# Relay_off_delay.net
KiCad netlist of a schematic drawn in Altium Designer
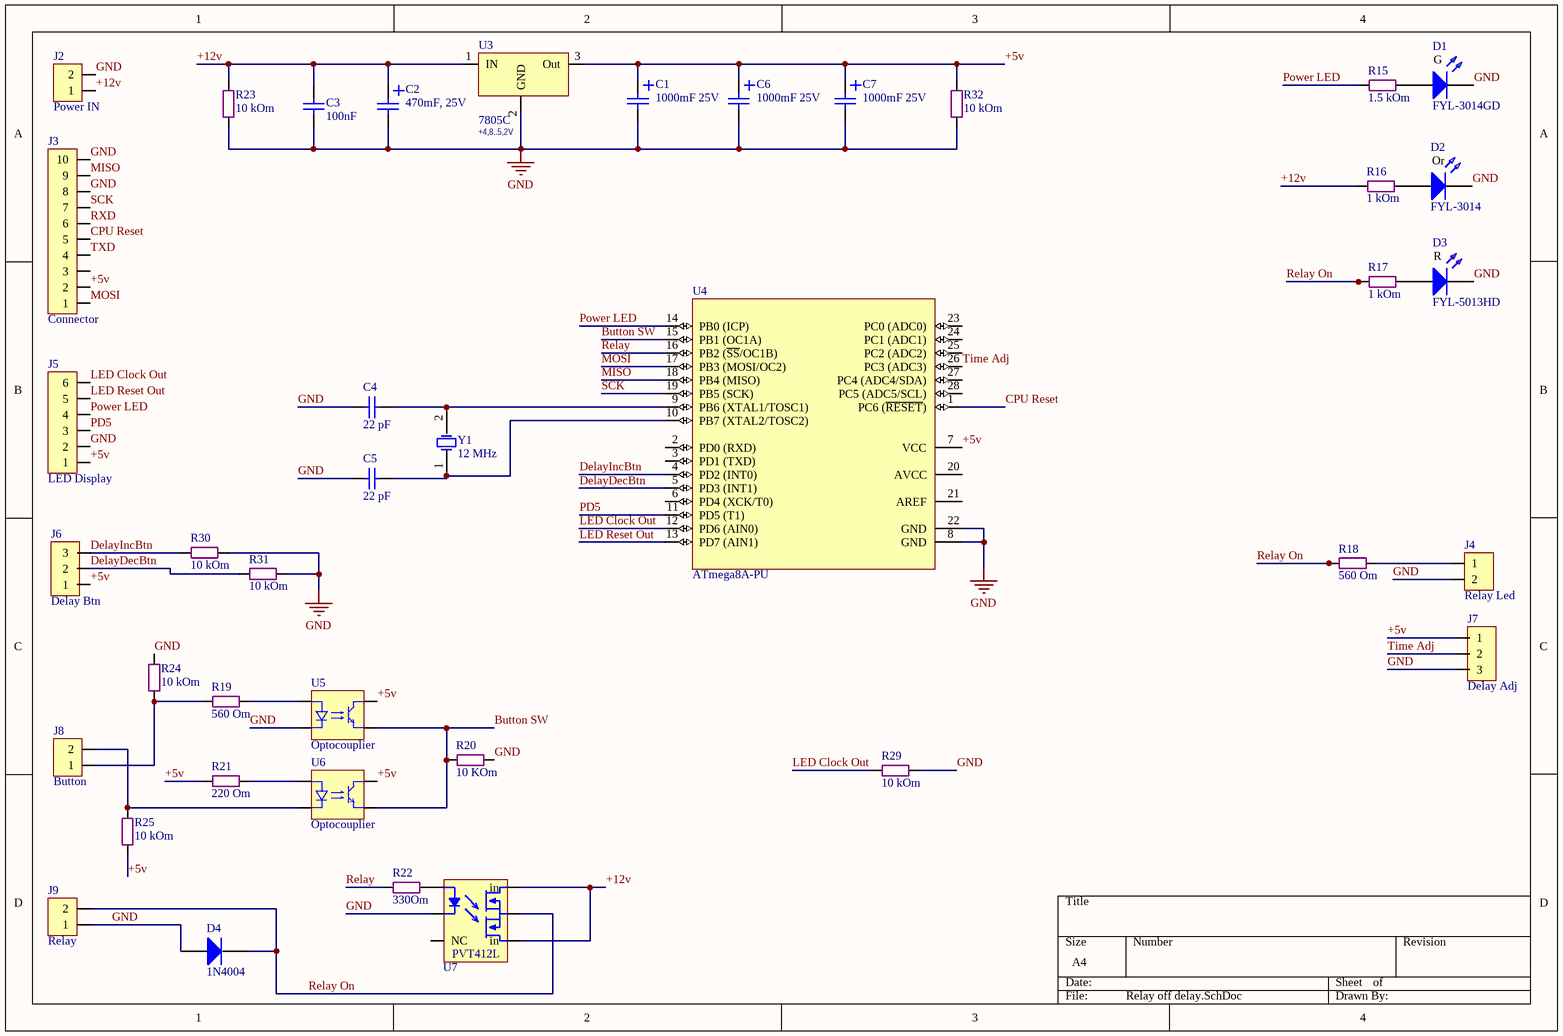
[diagram p0: Relay off delay.SchDoc]

(export (version "E")
  (design (tool "Eeschema 10.0.6"))
  (components
    (comp (ref "C1")
      (value "1000mF 25V")
      (footprint "Capacitor:Cap E p5.08mm D10.2mm (3p)")
      (description "Capacitor")
      (libsource (lib "Capacitor") (part "Cap E 1000mF x 25V"))
    )
    (comp (ref "C2")
      (value "470mF, 25V")
      (footprint "Capacitor:Cap E p3.5mm D8xH12")
      (description "Capacitor")
      (libsource (lib "Capacitor") (part "Cap E 470mF x 25V"))
    )
    (comp (ref "C3")
      (value "100nF")
      (footprint "Capacitor:Cap P5.08MM (3p) disk2")
      (description "Capacitor")
      (libsource (lib "Capacitor") (part "Cap Ceramic"))
    )
    (comp (ref "C4")
      (value "22 pF")
      (footprint "Capacitor:Cap P5.08MM (3p) disk2")
      (description "Capacitor")
      (libsource (lib "Capacitor") (part "Cap Ceramic"))
    )
    (comp (ref "C5")
      (value "22 pF")
      (footprint "Capacitor:Cap P5.08MM (3p) disk2")
      (description "Capacitor")
      (libsource (lib "Capacitor") (part "Cap Ceramic"))
    )
    (comp (ref "C6")
      (value "1000mF 25V")
      (footprint "Capacitor:Cap E p5.08mm D10.2mm (3p)")
      (description "Capacitor")
      (libsource (lib "Capacitor") (part "Cap E 1000mF x 25V"))
    )
    (comp (ref "C7")
      (value "1000mF 25V")
      (footprint "Capacitor:Cap E p5.08mm D10.2mm (3p)")
      (description "Capacitor")
      (libsource (lib "Capacitor") (part "Cap E 1000mF x 25V"))
    )
    (comp (ref "D1")
      (value "FYL-3014GD")
      (footprint "LED:LED Round 3mm Green")
      (description "2.1v 10mA, 15-30mCd")
      (libsource (lib "LED") (part "Led Round 3mm Green"))
    )
    (comp (ref "D2")
      (value "FYL-3014")
      (footprint "LED:LED Round 3mm Yellow")
      (description "2.1v 10mA, 30mCd")
      (libsource (lib "LED") (part "Led Round 3mm Orange"))
    )
    (comp (ref "D3")
      (value "FYL-5013HD")
      (footprint "LED:LED Round 3mm red")
      (description "2.25v 10mA, 5mCd")
      (libsource (lib "LED") (part "Led Round 3mm Red"))
    )
    (comp (ref "D4")
      (value "1N4004")
      (footprint "Diodes:Diode DO-35")
      (description "1 Amp General Purpose Rectifier")
      (libsource (lib "Diodes") (part "Diode 1N4004"))
    )
    (comp (ref "J2")
      (value "Power IN")
      (footprint "Connector:CWF-2 R")
      (description "CWF series")
      (libsource (lib "Connector") (part "CWF-2 (R)"))
    )
    (comp (ref "J3")
      (value "Connector")
      (footprint "Connector:LINE 2.54 x 10D (2 x 5) - BH")
      (description "Vert, Dbl line, Male")
      (libsource (lib "Connector") (part "PLD-10 (2 x 5)"))
    )
    (comp (ref "J4")
      (value "Relay Led")
      (footprint "Connector:CWF-2 R")
      (description "CWF series")
      (libsource (lib "") (part "CWF-2 (R)_1"))
    )
    (comp (ref "J5")
      (value "LED Display")
      (footprint "Connector:Molex Micro-Fit 3.0 - 6 pin D R")
      (description "Horisontal, Dbl line, Male - 3mm")
      (libsource (lib "Connector") (part "Micro-Fit 6R (2x3)"))
    )
    (comp (ref "J6")
      (value "Delay Btn")
      (footprint "Connector:WF-3")
      (description "Standart Fan MB's Connector")
      (libsource (lib "") (part "WF-3_1"))
    )
    (comp (ref "J7")
      (value "Delay Adj")
      (footprint "Connector:WF-3")
      (description "Standart Fan MB's Connector")
      (libsource (lib "Connector") (part "WF-3"))
    )
    (comp (ref "J8")
      (value "Button")
      (footprint "Connector:CWF-2 R")
      (description "CWF series")
      (libsource (lib "Connector") (part "CWF-2 (R)"))
    )
    (comp (ref "J9")
      (value "Relay")
      (footprint "Connector:CWF-2 R")
      (description "CWF series")
      (libsource (lib "Connector") (part "CWF-2 (R)"))
    )
    (comp (ref "R15")
      (value "1.5 kOm")
      (footprint "SMD 0805 (2012)")
      (libsource (lib "PassiveComponents") (part "Res SMD 0805"))
    )
    (comp (ref "R16")
      (value "1 kOm")
      (footprint "SMD 0805 (2012)")
      (libsource (lib "PassiveComponents") (part "Res SMD 0805"))
    )
    (comp (ref "R17")
      (value "1 kOm")
      (footprint "SMD 0805 (2012)")
      (libsource (lib "PassiveComponents") (part "Res SMD 0805"))
    )
    (comp (ref "R18")
      (value "560 Om")
      (footprint "SMD 0805 (2012)")
      (libsource (lib "PassiveComponents") (part "Res SMD 0805"))
    )
    (comp (ref "R19")
      (value "560 Om")
      (footprint "SMD 0805 (2012)")
      (libsource (lib "PassiveComponents") (part "Res SMD 0805"))
    )
    (comp (ref "R20")
      (value "10 KOm")
      (footprint "SMD 0805 (2012)")
      (libsource (lib "PassiveComponents") (part "Res SMD 0805"))
    )
    (comp (ref "R21")
      (value "220 Om")
      (footprint "SMD 0805 (2012)")
      (libsource (lib "PassiveComponents") (part "Res SMD 0805"))
    )
    (comp (ref "R22")
      (value "330Om")
      (footprint "PassiveComponents:SMD 1206 (3216)")
      (libsource (lib "PassiveComponents") (part "Res All Types"))
    )
    (comp (ref "R23")
      (value "10 kOm")
      (footprint "PassiveComponents:SMD 0805 (2012)")
      (libsource (lib "PassiveComponents") (part "Res All Types"))
    )
    (comp (ref "R24")
      (value "10 kOm")
      (footprint "PassiveComponents:SMD 0805 (2012)")
      (libsource (lib "PassiveComponents") (part "Res All Types"))
    )
    (comp (ref "R25")
      (value "10 kOm")
      (footprint "PassiveComponents:SMD 0805 (2012)")
      (libsource (lib "PassiveComponents") (part "Res All Types"))
    )
    (comp (ref "R29")
      (value "10 kOm")
      (footprint "PassiveComponents:Res p7.62 (4p) 0.25w")
      (libsource (lib "PassiveComponents") (part "Res All Types"))
    )
    (comp (ref "R30")
      (value "10 kOm")
      (footprint "PassiveComponents:Res p7.62 (4p) 0.25w")
      (libsource (lib "PassiveComponents") (part "Res All Types"))
    )
    (comp (ref "R31")
      (value "10 kOm")
      (footprint "PassiveComponents:Res p7.62 (4p) 0.25w")
      (libsource (lib "PassiveComponents") (part "Res All Types"))
    )
    (comp (ref "R32")
      (value "10 kOm")
      (footprint "PassiveComponents:SMD 0805 (2012)")
      (libsource (lib "PassiveComponents") (part "Res All Types"))
    )
    (comp (ref "U3")
      (value "7805C")
      (footprint "GeneralCases:D-PAK")
      (description "Voltage Regulator")
      (fields (field (name "MANUFACTURER") "Интеграл") (field (name "V OUT") "+4,8..5,2V"))
      (libsource (lib "PowerAdjusment") (part "7805C"))
    )
    (comp (ref "U4")
      (value "ATmega8A-PU")
      (footprint "28P3")
      (fields (field (name "PUBLISHER") "Altium Limited"))
      (libsource (lib "Atmel Microcontroller 8-Bit megaAVR") (part "ATmega8A-PU"))
    )
    (comp (ref "U5")
      (value "Optocouplier")
      (footprint "GeneralCases:DIP-4")
      (libsource (lib "Transistor") (part "Optocouplier LTV 817B"))
    )
    (comp (ref "U6")
      (value "Optocouplier")
      (footprint "GeneralCases:DIP-4")
      (libsource (lib "Transistor") (part "Optocouplier LTV 817B"))
    )
    (comp (ref "U7")
      (value "PVT412L")
      (footprint "GeneralCases:DIP-6")
      (description "Opto relay 2 chanel, MOSFET")
      (libsource (lib "Transistor") (part "Opto Rlay PVT412L"))
    )
    (comp (ref "Y1")
      (value "12 MHz")
      (footprint "PassiveComponents:XTAL - 2")
      (description "Crystal Oscillator")
      (fields (field (name "PUBLISHER") "Altium Limited"))
      (libsource (lib "PassiveComponents") (part "XTAL"))
    )
  )
  (nets
    (net (code "1") (name "/+5v") (class "Default")
      (node (ref "C1") (pin "1") (pinfunction "1_1") (pintype "passive"))
      (node (ref "C6") (pin "1") (pinfunction "1_1") (pintype "passive"))
      (node (ref "C7") (pin "1") (pinfunction "1_1") (pintype "passive"))
      (node (ref "J3") (pin "2") (pinfunction "2_2") (pintype "passive"))
      (node (ref "J5") (pin "1") (pinfunction "1_1") (pintype "passive"))
      (node (ref "J6") (pin "1") (pinfunction "1_1") (pintype "passive"))
      (node (ref "J7") (pin "1") (pinfunction "1_1") (pintype "passive"))
      (node (ref "R21") (pin "1") (pinfunction "1_1") (pintype "passive"))
      (node (ref "R25") (pin "1") (pinfunction "1_1") (pintype "passive"))
      (node (ref "R32") (pin "2") (pinfunction "2_2") (pintype "passive"))
      (node (ref "U3") (pin "3") (pinfunction "Out_3") (pintype "power_in"))
      (node (ref "U4") (pin "7") (pinfunction "VCC_7") (pintype "power_in"))
      (node (ref "U5") (pin "3") (pinfunction "3_3") (pintype "passive"))
      (node (ref "U6") (pin "3") (pinfunction "3_3") (pintype "passive"))
    )
    (net (code "2") (name "/+12v") (class "Default")
      (node (ref "C2") (pin "1") (pinfunction "1_1") (pintype "passive"))
      (node (ref "C3") (pin "1") (pinfunction "1_1") (pintype "passive"))
      (node (ref "J2") (pin "1") (pinfunction "1_1") (pintype "passive"))
      (node (ref "R16") (pin "1") (pinfunction "1_1") (pintype "passive"))
      (node (ref "R23") (pin "2") (pinfunction "2_2") (pintype "passive"))
      (node (ref "U3") (pin "1") (pinfunction "IN_1") (pintype "power_in"))
      (node (ref "U7") (pin "4") (pinfunction "in_4") (pintype "passive"))
      (node (ref "U7") (pin "6") (pinfunction "in_6") (pintype "passive"))
    )
    (net (code "3") (name "/Button SW") (class "Default")
      (node (ref "R20") (pin "1") (pinfunction "1_1") (pintype "passive"))
      (node (ref "U4") (pin "15") (pinfunction "PB1_(OC1A)_15") (pintype "bidirectional"))
      (node (ref "U5") (pin "4") (pinfunction "4_4") (pintype "passive"))
      (node (ref "U6") (pin "4") (pinfunction "4_4") (pintype "passive"))
    )
    (net (code "4") (name "/CPU Reset") (class "Default")
      (node (ref "J3") (pin "5") (pinfunction "5_5") (pintype "passive"))
      (node (ref "U4") (pin "1") (pinfunction "PC6_(~{RESET})_1") (pintype "bidirectional"))
    )
    (net (code "5") (name "/DelayDecBtn") (class "Default")
      (node (ref "J6") (pin "2") (pinfunction "2_2") (pintype "passive"))
      (node (ref "R31") (pin "2") (pinfunction "2_2") (pintype "passive"))
      (node (ref "U4") (pin "5") (pinfunction "PD3_(INT1)_5") (pintype "bidirectional"))
    )
    (net (code "6") (name "/DelayIncBtn") (class "Default")
      (node (ref "J6") (pin "3") (pinfunction "3_3") (pintype "passive"))
      (node (ref "R30") (pin "2") (pinfunction "2_2") (pintype "passive"))
      (node (ref "U4") (pin "4") (pinfunction "PD2_(INT0)_4") (pintype "bidirectional"))
    )
    (net (code "7") (name "/LED Clock Out") (class "Default")
      (node (ref "J5") (pin "6") (pinfunction "6_6") (pintype "passive"))
      (node (ref "R29") (pin "1") (pinfunction "1_1") (pintype "passive"))
      (node (ref "U4") (pin "12") (pinfunction "PD6_(AIN0)_12") (pintype "bidirectional"))
    )
    (net (code "8") (name "/LED Reset Out") (class "Default")
      (node (ref "J5") (pin "5") (pinfunction "5_5") (pintype "passive"))
      (node (ref "U4") (pin "13") (pinfunction "PD7_(AIN1)_13") (pintype "bidirectional"))
    )
    (net (code "9") (name "/MISO") (class "Default")
      (node (ref "J3") (pin "9") (pinfunction "9_9") (pintype "passive"))
      (node (ref "U4") (pin "18") (pinfunction "PB4_(MISO)_18") (pintype "bidirectional"))
    )
    (net (code "10") (name "/MOSI") (class "Default")
      (node (ref "J3") (pin "1") (pinfunction "1_1") (pintype "passive"))
      (node (ref "U4") (pin "17") (pinfunction "PB3_(MOSI/OC2)_17") (pintype "bidirectional"))
    )
    (net (code "11") (name "/PD5") (class "Default")
      (node (ref "J5") (pin "3") (pinfunction "3_3") (pintype "passive"))
      (node (ref "U4") (pin "11") (pinfunction "PD5_(T1)_11") (pintype "bidirectional"))
    )
    (net (code "12") (name "/Power LED") (class "Default")
      (node (ref "J5") (pin "4") (pinfunction "4_4") (pintype "passive"))
      (node (ref "R15") (pin "1") (pinfunction "1_1") (pintype "passive"))
      (node (ref "U4") (pin "14") (pinfunction "PB0_(ICP)_14") (pintype "bidirectional"))
    )
    (net (code "13") (name "/RXD") (class "Default")
      (node (ref "J3") (pin "6") (pinfunction "6_6") (pintype "passive"))
    )
    (net (code "14") (name "/Relay") (class "Default")
      (node (ref "R22") (pin "1") (pinfunction "1_1") (pintype "passive"))
      (node (ref "U4") (pin "16") (pinfunction "PB2_(~{SS}/OC1B)_16") (pintype "bidirectional"))
    )
    (net (code "15") (name "/Relay On") (class "Default")
      (node (ref "D4") (pin "K") (pinfunction "K_K") (pintype "passive"))
      (node (ref "J9") (pin "2") (pinfunction "2_2") (pintype "passive"))
      (node (ref "R17") (pin "1") (pinfunction "1_1") (pintype "passive"))
      (node (ref "R18") (pin "1") (pinfunction "1_1") (pintype "passive"))
      (node (ref "U7") (pin "5") (pinfunction "5_5") (pintype "passive"))
    )
    (net (code "16") (name "/SCK") (class "Default")
      (node (ref "J3") (pin "7") (pinfunction "7_7") (pintype "passive"))
      (node (ref "U4") (pin "19") (pinfunction "PB5_(SCK)_19") (pintype "bidirectional"))
    )
    (net (code "17") (name "/TXD") (class "Default")
      (node (ref "J3") (pin "4") (pinfunction "4_4") (pintype "passive"))
    )
    (net (code "18") (name "/Time Adj") (class "Default")
      (node (ref "J7") (pin "2") (pinfunction "2_2") (pintype "passive"))
      (node (ref "U4") (pin "26") (pinfunction "PC3_(ADC3)_26") (pintype "bidirectional"))
    )
    (net (code "19") (name "GND") (class "Default")
      (node (ref "C1") (pin "2") (pinfunction "2_2") (pintype "passive"))
      (node (ref "C2") (pin "2") (pinfunction "2_2") (pintype "passive"))
      (node (ref "C3") (pin "2") (pinfunction "2_2") (pintype "passive"))
      (node (ref "C4") (pin "1") (pinfunction "1_1") (pintype "passive"))
      (node (ref "C5") (pin "1") (pinfunction "1_1") (pintype "passive"))
      (node (ref "C6") (pin "2") (pinfunction "2_2") (pintype "passive"))
      (node (ref "C7") (pin "2") (pinfunction "2_2") (pintype "passive"))
      (node (ref "D1") (pin "K") (pinfunction "K_K") (pintype "passive"))
      (node (ref "D2") (pin "K") (pinfunction "K_K") (pintype "passive"))
      (node (ref "D3") (pin "K") (pinfunction "K_K") (pintype "passive"))
      (node (ref "D4") (pin "A") (pinfunction "A_A") (pintype "passive"))
      (node (ref "J2") (pin "2") (pinfunction "2_2") (pintype "passive"))
      (node (ref "J3") (pin "10") (pinfunction "10_10") (pintype "passive"))
      (node (ref "J3") (pin "8") (pinfunction "8_8") (pintype "passive"))
      (node (ref "J4") (pin "2") (pinfunction "2_2") (pintype "passive"))
      (node (ref "J5") (pin "2") (pinfunction "2_2") (pintype "passive"))
      (node (ref "J7") (pin "3") (pinfunction "3_3") (pintype "passive"))
      (node (ref "J9") (pin "1") (pinfunction "1_1") (pintype "passive"))
      (node (ref "R20") (pin "2") (pinfunction "2_2") (pintype "passive"))
      (node (ref "R23") (pin "1") (pinfunction "1_1") (pintype "passive"))
      (node (ref "R24") (pin "2") (pinfunction "2_2") (pintype "passive"))
      (node (ref "R29") (pin "2") (pinfunction "2_2") (pintype "passive"))
      (node (ref "R30") (pin "1") (pinfunction "1_1") (pintype "passive"))
      (node (ref "R31") (pin "1") (pinfunction "1_1") (pintype "passive"))
      (node (ref "R32") (pin "1") (pinfunction "1_1") (pintype "passive"))
      (node (ref "U3") (pin "2") (pinfunction "GND_2") (pintype "passive"))
      (node (ref "U4") (pin "22") (pinfunction "GND_22") (pintype "power_in"))
      (node (ref "U4") (pin "8") (pinfunction "GND_8") (pintype "power_in"))
      (node (ref "U5") (pin "2") (pinfunction "2_2") (pintype "passive"))
      (node (ref "U7") (pin "2") (pinfunction "2_2") (pintype "passive"))
    )
    (net (code "20") (name "Net-(D1-PadA)") (class "Default")
      (node (ref "D1") (pin "A") (pinfunction "A_A") (pintype "passive"))
      (node (ref "R15") (pin "2") (pinfunction "2_2") (pintype "passive"))
    )
    (net (code "21") (name "Net-(D2-PadA)") (class "Default")
      (node (ref "D2") (pin "A") (pinfunction "A_A") (pintype "passive"))
      (node (ref "R16") (pin "2") (pinfunction "2_2") (pintype "passive"))
    )
    (net (code "22") (name "Net-(D3-PadA)") (class "Default")
      (node (ref "D3") (pin "A") (pinfunction "A_A") (pintype "passive"))
      (node (ref "R17") (pin "2") (pinfunction "2_2") (pintype "passive"))
    )
    (net (code "23") (name "Net-(J4-Pad1)") (class "Default")
      (node (ref "J4") (pin "1") (pinfunction "1_1") (pintype "passive"))
      (node (ref "R18") (pin "2") (pinfunction "2_2") (pintype "passive"))
    )
    (net (code "24") (name "Net-(J8-Pad1)") (class "Default")
      (node (ref "J8") (pin "1") (pinfunction "1_1") (pintype "passive"))
      (node (ref "R19") (pin "1") (pinfunction "1_1") (pintype "passive"))
      (node (ref "R24") (pin "1") (pinfunction "1_1") (pintype "passive"))
    )
    (net (code "25") (name "Net-(J8-Pad2)") (class "Default")
      (node (ref "J8") (pin "2") (pinfunction "2_2") (pintype "passive"))
      (node (ref "R25") (pin "2") (pinfunction "2_2") (pintype "passive"))
      (node (ref "U6") (pin "2") (pinfunction "2_2") (pintype "passive"))
    )
    (net (code "26") (name "Net-(R19-Pad2)") (class "Default")
      (node (ref "R19") (pin "2") (pinfunction "2_2") (pintype "passive"))
      (node (ref "U5") (pin "1") (pinfunction "1_1") (pintype "passive"))
    )
    (net (code "27") (name "Net-(R21-Pad2)") (class "Default")
      (node (ref "R21") (pin "2") (pinfunction "2_2") (pintype "passive"))
      (node (ref "U6") (pin "1") (pinfunction "1_1") (pintype "passive"))
    )
    (net (code "28") (name "Net-(R22-Pad2)") (class "Default")
      (node (ref "R22") (pin "2") (pinfunction "2_2") (pintype "passive"))
      (node (ref "U7") (pin "1") (pinfunction "1_1") (pintype "passive"))
    )
    (net (code "29") (name "Net-(U4-PB6_(XTAL1{slash}TOSC1))") (class "Default")
      (node (ref "C4") (pin "2") (pinfunction "2_2") (pintype "passive"))
      (node (ref "U4") (pin "9") (pinfunction "PB6_(XTAL1/TOSC1)_9") (pintype "bidirectional"))
      (node (ref "Y1") (pin "2") (pinfunction "OSC2_2") (pintype "passive"))
    )
    (net (code "30") (name "Net-(U4-PB7_(XTAL2{slash}TOSC2))") (class "Default")
      (node (ref "C5") (pin "2") (pinfunction "2_2") (pintype "passive"))
      (node (ref "U4") (pin "10") (pinfunction "PB7_(XTAL2/TOSC2)_10") (pintype "bidirectional"))
      (node (ref "Y1") (pin "1") (pinfunction "OSC1_1") (pintype "passive"))
    )
    (net (code "31") (name "unconnected-(J3-Pad3)") (class "Default")
      (node (ref "J3") (pin "3") (pinfunction "3_3") (pintype "passive"))
    )
    (net (code "32") (name "unconnected-(U4-AREF-Pad21)") (class "Default")
      (node (ref "U4") (pin "21") (pinfunction "AREF_21") (pintype "passive"))
    )
    (net (code "33") (name "unconnected-(U4-AVCC-Pad20)") (class "Default")
      (node (ref "U4") (pin "20") (pinfunction "AVCC_20") (pintype "power_in"))
    )
    (net (code "34") (name "unconnected-(U4-PC0_(ADC0)-Pad23)") (class "Default")
      (node (ref "U4") (pin "23") (pinfunction "PC0_(ADC0)_23") (pintype "bidirectional"))
    )
    (net (code "35") (name "unconnected-(U4-PC1_(ADC1)-Pad24)") (class "Default")
      (node (ref "U4") (pin "24") (pinfunction "PC1_(ADC1)_24") (pintype "bidirectional"))
    )
    (net (code "36") (name "unconnected-(U4-PC2_(ADC2)-Pad25)") (class "Default")
      (node (ref "U4") (pin "25") (pinfunction "PC2_(ADC2)_25") (pintype "bidirectional"))
    )
    (net (code "37") (name "unconnected-(U4-PC4_(ADC4{slash}SDA)-Pad27)") (class "Default")
      (node (ref "U4") (pin "27") (pinfunction "PC4_(ADC4/SDA)_27") (pintype "bidirectional"))
    )
    (net (code "38") (name "unconnected-(U4-PC5_(ADC5{slash}SCL)-Pad28)") (class "Default")
      (node (ref "U4") (pin "28") (pinfunction "PC5_(ADC5/SCL)_28") (pintype "bidirectional"))
    )
    (net (code "39") (name "unconnected-(U4-PD0_(RXD)-Pad2)") (class "Default")
      (node (ref "U4") (pin "2") (pinfunction "PD0_(RXD)_2") (pintype "bidirectional"))
    )
    (net (code "40") (name "unconnected-(U4-PD1_(TXD)-Pad3)") (class "Default")
      (node (ref "U4") (pin "3") (pinfunction "PD1_(TXD)_3") (pintype "bidirectional"))
    )
    (net (code "41") (name "unconnected-(U4-PD4_(XCK{slash}T0)-Pad6)") (class "Default")
      (node (ref "U4") (pin "6") (pinfunction "PD4_(XCK/T0)_6") (pintype "bidirectional"))
    )
    (net (code "42") (name "unconnected-(U7-NC-Pad3)") (class "Default")
      (node (ref "U7") (pin "3") (pinfunction "NC_3") (pintype "passive"))
    )
  )
)
